# pyr0-piezo_direct_extruder_board2_0_2.net
KiCad netlist of a schematic drawn in EAGLE
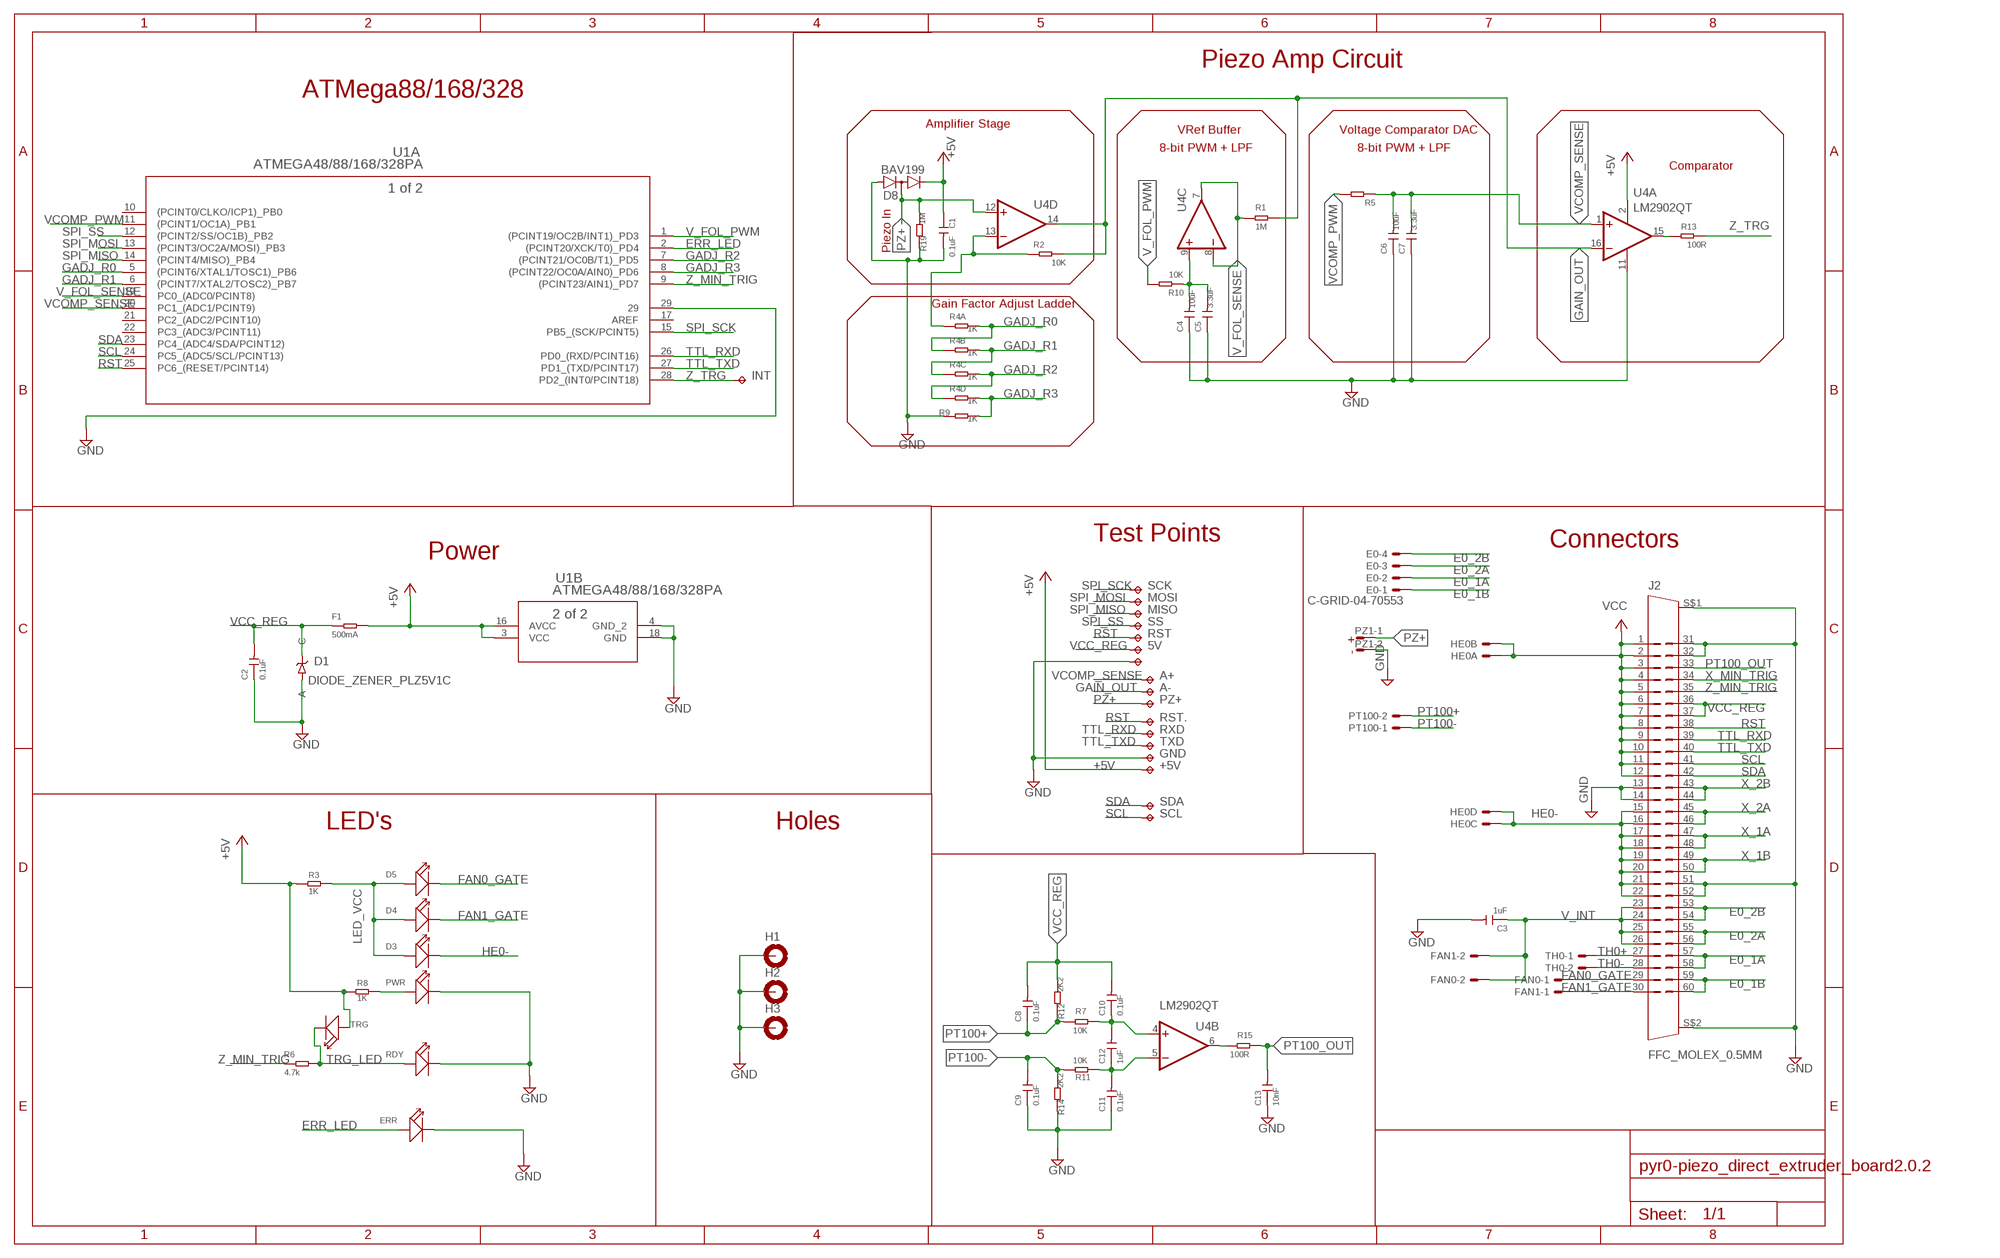
[diagram p0: schematic, sheet 1]

(export (version "E")
  (design (tool "Eeschema 10.0.6"))
  (components
    (comp (ref "+5V")
      (value "TPTP13SQ")
      (footprint "eagle-import:TP13SQ")
      (libsource (lib "eagle-import") (part "testpad_385_TPTP13SQ"))
    )
    (comp (ref "5V")
      (value "TPTP13SQ")
      (footprint "eagle-import:TP13SQ")
      (libsource (lib "eagle-import") (part "TPTP13SQ"))
    )
    (comp (ref "A+")
      (value "TPTP13SQ")
      (footprint "eagle-import:TP13SQ")
      (libsource (lib "eagle-import") (part "TPTP13SQ"))
    )
    (comp (ref "A-")
      (value "TPTP13SQ")
      (footprint "eagle-import:TP13SQ")
      (libsource (lib "eagle-import") (part "TPTP13SQ"))
    )
    (comp (ref "C1")
      (value "0.1uF")
      (footprint "eagle-import:CAPC1005X50")
      (libsource (lib "eagle-import") (part "CERAMIC-1NF-50V-10%-X7R(0402)CAP_0402"))
    )
    (comp (ref "C2")
      (value "0.1uF")
      (footprint "eagle-import:CAPC1005X50")
      (libsource (lib "eagle-import") (part "CERAMIC-1NF-50V-10%-X7R(0402)CAP_0402"))
    )
    (comp (ref "C3")
      (value "1uF")
      (footprint "eagle-import:CAPC1609X80")
      (libsource (lib "eagle-import") (part "SEEED-CAPACITOR_CERAMIC-10UF-25V-10%-X5R(0805)CAP_0603_GEN"))
    )
    (comp (ref "C4")
      (value "10uF")
      (footprint "eagle-import:CAPC1005X50")
      (libsource (lib "eagle-import") (part "CERAMIC-1NF-50V-10%-X7R(0402)CAP_0402"))
    )
    (comp (ref "C5")
      (value "3.3uF")
      (footprint "eagle-import:CAPC1609X80")
      (libsource (lib "eagle-import") (part "SEEED-CAPACITOR_CERAMIC-10UF-25V-10%-X5R(0805)CAP_0603_GEN"))
    )
    (comp (ref "C6")
      (value "10uF")
      (footprint "eagle-import:CAPC1005X50")
      (libsource (lib "eagle-import") (part "CERAMIC-1NF-50V-10%-X7R(0402)CAP_0402"))
    )
    (comp (ref "C7")
      (value "3.3uF")
      (footprint "eagle-import:CAPC1609X80")
      (libsource (lib "eagle-import") (part "SEEED-CAPACITOR_CERAMIC-10UF-25V-10%-X5R(0805)CAP_0603_GEN"))
    )
    (comp (ref "C8")
      (value "0.1uF")
      (footprint "eagle-import:CAPC1005X50")
      (libsource (lib "eagle-import") (part "CERAMIC-1NF-50V-10%-X7R(0402)CAP_0402"))
    )
    (comp (ref "C9")
      (value "0.1uF")
      (footprint "eagle-import:CAPC1005X50")
      (libsource (lib "eagle-import") (part "CERAMIC-1NF-50V-10%-X7R(0402)CAP_0402"))
    )
    (comp (ref "C10")
      (value "0.1uF")
      (footprint "eagle-import:CAPC1005X50")
      (libsource (lib "eagle-import") (part "CERAMIC-1NF-50V-10%-X7R(0402)CAP_0402"))
    )
    (comp (ref "C11")
      (value "0.1uF")
      (footprint "eagle-import:CAPC1005X50")
      (libsource (lib "eagle-import") (part "CERAMIC-1NF-50V-10%-X7R(0402)CAP_0402"))
    )
    (comp (ref "C12")
      (value "1uF")
      (footprint "eagle-import:CAPC1005X50")
      (libsource (lib "eagle-import") (part "CERAMIC-1NF-50V-10%-X7R(0402)CAP_0402"))
    )
    (comp (ref "C13")
      (value "10nF")
      (footprint "eagle-import:CAPC1005X50")
      (libsource (lib "eagle-import") (part "CERAMIC-1NF-50V-10%-X7R(0402)CAP_0402"))
    )
    (comp (ref "D1")
      (value "DIODE_ZENER_PLZ5V1C")
      (footprint "eagle-import:DO-219AC")
      (libsource (lib "eagle-import") (part "DIODE_ZENER_PLZ5V1C"))
    )
    (comp (ref "D3")
      (value "SEEED-LED_SMD-LED-CLEAR-BLUE(0603)LED_0603")
      (footprint "eagle-import:SEEED-LED_LED-0603")
      (libsource (lib "eagle-import") (part "SEEED-LED_SMD-LED-CLEAR-BLUE(0603)LED_0603"))
    )
    (comp (ref "D4")
      (value "SEEED-LED_SMD-LED-CLEAR-BLUE(0603)LED_0603")
      (footprint "eagle-import:SEEED-LED_LED-0603")
      (libsource (lib "eagle-import") (part "SEEED-LED_SMD-LED-CLEAR-BLUE(0603)LED_0603"))
    )
    (comp (ref "D5")
      (value "SEEED-LED_SMD-LED-CLEAR-BLUE(0603)LED_0603")
      (footprint "eagle-import:SEEED-LED_LED-0603")
      (libsource (lib "eagle-import") (part "SEEED-LED_SMD-LED-CLEAR-BLUE(0603)LED_0603"))
    )
    (comp (ref "D8")
      (value "BAV199")
      (footprint "eagle-import:SOT23")
      (libsource (lib "eagle-import") (part "BAV199"))
    )
    (comp (ref "E0")
      (value "C-GRID-04-70553")
      (footprint "eagle-import:70553-04")
      (fields (field (name "MF") "MOLEX"))
      (libsource (lib "eagle-import") (part "C-GRID-04-70553"))
    )
    (comp (ref "ERR")
      (value "SEEED-LED_SMD-LED-CLEAR-BLUE(0603)LED_0603")
      (footprint "eagle-import:SEEED-LED_LED-0603")
      (libsource (lib "eagle-import") (part "SEEED-LED_SMD-LED-CLEAR-BLUE(0603)LED_0603"))
    )
    (comp (ref "F1")
      (value "500mA")
      (footprint "eagle-import:SEEED-RESISTOR_R0603")
      (libsource (lib "eagle-import") (part "SEEED-RESISTOR_SMD-RES-1.5K-1%-1/10W(0603)DETAILED_MODEL"))
    )
    (comp (ref "FAN0")
      (value "CON-MOLEX-2P-1.27MM048")
      (footprint "eagle-import:53048-02")
      (fields (field (name "MF") "MOLEX") (field (name "MPN") "53048-0210"))
      (libsource (lib "eagle-import") (part "CON-MOLEX-2P-1.27MM048"))
    )
    (comp (ref "FAN1")
      (value "CON-MOLEX-2P-1.27MM048")
      (footprint "eagle-import:53048-02")
      (fields (field (name "MF") "MOLEX") (field (name "MPN") "53048-0210"))
      (libsource (lib "eagle-import") (part "CON-MOLEX-2P-1.27MM048"))
    )
    (comp (ref "GND")
      (value "TPTP13SQ")
      (footprint "eagle-import:TP13SQ")
      (libsource (lib "eagle-import") (part "testpad_385_TPTP13SQ"))
    )
    (comp (ref "H1")
      (value "HOLES_MOUNT-PAD-ROUND3.2")
      (footprint "eagle-import:HOLES_3,2-PAD")
      (libsource (lib "eagle-import") (part "HOLES_MOUNT-PAD-ROUND3.2"))
    )
    (comp (ref "H2")
      (value "HOLES_MOUNT-PAD-ROUND3.2")
      (footprint "eagle-import:HOLES_3,2-PAD")
      (libsource (lib "eagle-import") (part "HOLES_MOUNT-PAD-ROUND3.2"))
    )
    (comp (ref "H3")
      (value "HOLES_MOUNT-PAD-ROUND3.2")
      (footprint "eagle-import:HOLES_3,2-PAD")
      (libsource (lib "eagle-import") (part "HOLES_MOUNT-PAD-ROUND3.2"))
    )
    (comp (ref "HE0")
      (value "JST-2.54-2X2JST-DUPONT-2.54-2X2")
      (footprint "eagle-import:HDRRAR4W64P254_2X2_556X736X556B")
      (libsource (lib "eagle-import") (part "JST-2.54-2X2JST-DUPONT-2.54-2X2"))
    )
    (comp (ref "INT")
      (value "TPTP06R")
      (footprint "eagle-import:TP06R")
      (libsource (lib "eagle-import") (part "testpad_385_TPTP06R"))
    )
    (comp (ref "J2")
      (value "FFC_MOLEX_0.5MM")
      (footprint "eagle-import:FFC-60P_0.5_MOLEX_505110-6091")
      (libsource (lib "eagle-import") (part "FFC_MOLEX_0.5MM"))
    )
    (comp (ref "MISO")
      (value "TPTP13SQ")
      (footprint "eagle-import:TP13SQ")
      (libsource (lib "eagle-import") (part "TPTP13SQ"))
    )
    (comp (ref "MOSI")
      (value "TPTP13SQ")
      (footprint "eagle-import:TP13SQ")
      (libsource (lib "eagle-import") (part "TPTP13SQ"))
    )
    (comp (ref "PT100")
      (value "CON-MOLEX-2P-1.27MM048")
      (footprint "eagle-import:53048-02")
      (fields (field (name "MF") "MOLEX") (field (name "MPN") "53048-0210"))
      (libsource (lib "eagle-import") (part "CON-MOLEX-2P-1.27MM048"))
    )
    (comp (ref "PWR")
      (value "SEEED-LED_SMD-LED-CLEAR-BLUE(0603)LED_0603")
      (footprint "eagle-import:SEEED-LED_LED-0603")
      (libsource (lib "eagle-import") (part "SEEED-LED_SMD-LED-CLEAR-BLUE(0603)LED_0603"))
    )
    (comp (ref "PZ+")
      (value "TPTP13SQ")
      (footprint "eagle-import:TP13SQ")
      (libsource (lib "eagle-import") (part "TPTP13SQ"))
    )
    (comp (ref "PZ1")
      (value "CON-MOLEX-2P-1.27MM048")
      (footprint "eagle-import:53048-02")
      (fields (field (name "MF") "MOLEX") (field (name "MPN") "53048-0210"))
      (libsource (lib "eagle-import") (part "CON-MOLEX-2P-1.27MM048"))
    )
    (comp (ref "R1")
      (value "1M")
      (footprint "eagle-import:R0402")
      (fields (field (name "MPN") "RC0402JR-070RL"))
      (libsource (lib "eagle-import") (part "SMD-RES-0R-5%-1/16W(0402)"))
    )
    (comp (ref "R2")
      (value "10K")
      (footprint "eagle-import:R0402")
      (fields (field (name "MPN") "RC0402JR-070RL"))
      (libsource (lib "eagle-import") (part "SMD-RES-0R-5%-1/16W(0402)"))
    )
    (comp (ref "R3")
      (value "1K")
      (footprint "eagle-import:R0402")
      (fields (field (name "MPN") "RC0402JR-070RL"))
      (libsource (lib "eagle-import") (part "SMD-RES-0R-5%-1/16W(0402)"))
    )
    (comp (ref "R4")
      (value "1K")
      (footprint "eagle-import:EXBN8V")
      (libsource (lib "eagle-import") (part "RESISTOR_NETWORK_X40804"))
    )
    (comp (ref "R5")
      (value "10K")
      (footprint "eagle-import:SEEED-RESISTOR_R0603")
      (libsource (lib "eagle-import") (part "SEEED-RESISTOR_SMD-RES-1.5K-1%-1/10W(0603)DETAILED_MODEL"))
    )
    (comp (ref "R6")
      (value "4.7k")
      (footprint "eagle-import:R0402")
      (fields (field (name "MPN") "RC0402JR-070RL"))
      (libsource (lib "eagle-import") (part "SMD-RES-0R-5%-1/16W(0402)"))
    )
    (comp (ref "R7")
      (value "10K")
      (footprint "eagle-import:R0402")
      (fields (field (name "MPN") "RC0402JR-070RL"))
      (libsource (lib "eagle-import") (part "SMD-RES-0R-5%-1/16W(0402)"))
    )
    (comp (ref "R8")
      (value "1K")
      (footprint "eagle-import:R0402")
      (fields (field (name "MPN") "RC0402JR-070RL"))
      (libsource (lib "eagle-import") (part "SMD-RES-0R-5%-1/16W(0402)"))
    )
    (comp (ref "R9")
      (value "1K")
      (footprint "eagle-import:R0402")
      (fields (field (name "MPN") "RC0402JR-070RL"))
      (libsource (lib "eagle-import") (part "SMD-RES-0R-5%-1/16W(0402)"))
    )
    (comp (ref "R10")
      (value "10K")
      (footprint "eagle-import:R0402")
      (fields (field (name "MPN") "RC0402JR-070RL"))
      (libsource (lib "eagle-import") (part "SMD-RES-0R-5%-1/16W(0402)"))
    )
    (comp (ref "R11")
      (value "10K")
      (footprint "eagle-import:R0402")
      (fields (field (name "MPN") "RC0402JR-070RL"))
      (libsource (lib "eagle-import") (part "SMD-RES-0R-5%-1/16W(0402)"))
    )
    (comp (ref "R12")
      (value "2K2")
      (footprint "eagle-import:R0402")
      (fields (field (name "MPN") "RC0402JR-070RL"))
      (libsource (lib "eagle-import") (part "SMD-RES-0R-5%-1/16W(0402)"))
    )
    (comp (ref "R13")
      (value "100R")
      (footprint "eagle-import:R0402")
      (fields (field (name "MPN") "RC0402JR-070RL"))
      (libsource (lib "eagle-import") (part "SMD-RES-0R-5%-1/16W(0402)"))
    )
    (comp (ref "R14")
      (value "2K2")
      (footprint "eagle-import:R0402")
      (fields (field (name "MPN") "RC0402JR-070RL"))
      (libsource (lib "eagle-import") (part "SMD-RES-0R-5%-1/16W(0402)"))
    )
    (comp (ref "R15")
      (value "100R")
      (footprint "eagle-import:R0402")
      (fields (field (name "MPN") "RC0402JR-070RL"))
      (libsource (lib "eagle-import") (part "SMD-RES-0R-5%-1/16W(0402)"))
    )
    (comp (ref "R19")
      (value "1M")
      (footprint "eagle-import:R0402")
      (fields (field (name "MPN") "RC0402JR-070RL"))
      (libsource (lib "eagle-import") (part "SMD-RES-0R-5%-1/16W(0402)"))
    )
    (comp (ref "RDY")
      (value "SEEED-LED_SMD-LED-CLEAR-BLUE(0603)LED_0603")
      (footprint "eagle-import:SEEED-LED_LED-0603")
      (libsource (lib "eagle-import") (part "SEEED-LED_SMD-LED-CLEAR-BLUE(0603)LED_0603"))
    )
    (comp (ref "RST")
      (value "TPTP13SQ")
      (footprint "eagle-import:TP13SQ")
      (libsource (lib "eagle-import") (part "TPTP13SQ"))
    )
    (comp (ref "RST.")
      (value "TPTP13SQ")
      (footprint "eagle-import:TP13SQ")
      (libsource (lib "eagle-import") (part "testpad_385_TPTP13SQ"))
    )
    (comp (ref "RXD")
      (value "TPTP13SQ")
      (footprint "eagle-import:TP13SQ")
      (libsource (lib "eagle-import") (part "testpad_385_TPTP13SQ"))
    )
    (comp (ref "SCK")
      (value "TPTP13SQ")
      (footprint "eagle-import:TP13SQ")
      (libsource (lib "eagle-import") (part "TPTP13SQ"))
    )
    (comp (ref "SCL")
      (value "TPTP13SQ")
      (footprint "eagle-import:TP13SQ")
      (libsource (lib "eagle-import") (part "testpad_385_TPTP13SQ"))
    )
    (comp (ref "SDA")
      (value "TPTP13SQ")
      (footprint "eagle-import:TP13SQ")
      (libsource (lib "eagle-import") (part "testpad_385_TPTP13SQ"))
    )
    (comp (ref "SS")
      (value "TPTP06R")
      (footprint "eagle-import:TP06R")
      (libsource (lib "eagle-import") (part "testpad_385_TPTP06R"))
    )
    (comp (ref "TH0")
      (value "CON-MOLEX-2P-1.27MM048")
      (footprint "eagle-import:53048-02")
      (fields (field (name "MF") "MOLEX") (field (name "MPN") "53048-0210"))
      (libsource (lib "eagle-import") (part "CON-MOLEX-2P-1.27MM048"))
    )
    (comp (ref "TRG")
      (value "SEEED-LED_SMD-LED-CLEAR-BLUE(0603)LED_0603")
      (footprint "eagle-import:SEEED-LED_LED-0603")
      (libsource (lib "eagle-import") (part "SEEED-LED_SMD-LED-CLEAR-BLUE(0603)LED_0603"))
    )
    (comp (ref "TXD")
      (value "TPTP13SQ")
      (footprint "eagle-import:TP13SQ")
      (libsource (lib "eagle-import") (part "testpad_385_TPTP13SQ"))
    )
    (comp (ref "U1")
      (value "ATMEGA48/88/168/328PA")
      (footprint "eagle-import:28M1")
      (fields (field (name "MANUFACTURER_PART_NUMBER") "ATMEGA48PAMMHR"))
      (libsource (lib "eagle-import") (part "ATMEGA48/88/168/328PA"))
    )
    (comp (ref "U4")
      (value "LM2902QT")
      (footprint "eagle-import:QFN16")
      (libsource (lib "eagle-import") (part "LM2902QT"))
    )
    (comp (ref "⏚")
      (value "TPTP13SQ")
      (footprint "eagle-import:TP13SQ")
      (libsource (lib "eagle-import") (part "testpad_385_TPTP13SQ"))
    )
  )
  (nets
    (net (code "1") (name "+5V") (class "Default")
      (node (ref "+5V") (pin "TP") (pinfunction "TP_TP") (pintype "input"))
      (node (ref "C1") (pin "1") (pinfunction "1_1") (pintype "passive"))
      (node (ref "D8") (pin "2") (pinfunction "C_2") (pintype "passive"))
      (node (ref "F1") (pin "2") (pinfunction "2_2") (pintype "passive"))
      (node (ref "R3") (pin "1") (pinfunction "1_1") (pintype "passive"))
      (node (ref "R8") (pin "1") (pinfunction "1_1") (pintype "passive"))
      (node (ref "TRG") (pin "+") (pinfunction "+_+") (pintype "passive"))
      (node (ref "U1") (pin "16") (pinfunction "AVCC_16") (pintype "power_in"))
      (node (ref "U1") (pin "3") (pinfunction "VCC_3") (pintype "power_in"))
      (node (ref "U4") (pin "2") (pinfunction "V+_2") (pintype "power_in"))
    )
    (net (code "2") (name "/E0_1A") (class "Default")
      (node (ref "E0") (pin "2") (pinfunction "S_2") (pintype "passive"))
      (node (ref "J2") (pin "57") (pinfunction "63_57") (pintype "passive"))
      (node (ref "J2") (pin "58") (pinfunction "64_58") (pintype "passive"))
    )
    (net (code "3") (name "/E0_1B") (class "Default")
      (node (ref "E0") (pin "1") (pinfunction "S_1") (pintype "passive"))
      (node (ref "J2") (pin "59") (pinfunction "65_59") (pintype "passive"))
      (node (ref "J2") (pin "60") (pinfunction "66_60") (pintype "passive"))
    )
    (net (code "4") (name "/E0_2A") (class "Default")
      (node (ref "E0") (pin "3") (pinfunction "S_3") (pintype "passive"))
      (node (ref "J2") (pin "55") (pinfunction "61_55") (pintype "passive"))
      (node (ref "J2") (pin "56") (pinfunction "62_56") (pintype "passive"))
    )
    (net (code "5") (name "/E0_2B") (class "Default")
      (node (ref "E0") (pin "4") (pinfunction "S_4") (pintype "passive"))
      (node (ref "J2") (pin "53") (pinfunction "59_53") (pintype "passive"))
      (node (ref "J2") (pin "54") (pinfunction "60_54") (pintype "passive"))
    )
    (net (code "6") (name "/ERR_LED") (class "Default")
      (node (ref "ERR") (pin "+") (pinfunction "+_+") (pintype "passive"))
      (node (ref "U1") (pin "2") (pinfunction "(PCINT20/XCK/T0)_PD4_2") (pintype "bidirectional"))
    )
    (net (code "7") (name "/FAN0_GATE") (class "Default")
      (node (ref "D5") (pin "-") (pinfunction "-_-") (pintype "passive"))
      (node (ref "FAN0") (pin "1") (pinfunction "S_1") (pintype "passive"))
      (node (ref "J2") (pin "29") (pinfunction "31_29") (pintype "passive"))
    )
    (net (code "8") (name "/FAN1_GATE") (class "Default")
      (node (ref "D4") (pin "-") (pinfunction "-_-") (pintype "passive"))
      (node (ref "FAN1") (pin "1") (pinfunction "S_1") (pintype "passive"))
      (node (ref "J2") (pin "30") (pinfunction "32_30") (pintype "passive"))
    )
    (net (code "9") (name "/GADJ_R0") (class "Default")
      (node (ref "R4") (pin "2") (pinfunction "1_2") (pintype "passive"))
      (node (ref "R4") (pin "8") (pinfunction "2_8") (pintype "passive"))
      (node (ref "U1") (pin "5") (pinfunction "(PCINT6/XTAL1/TOSC1)_PB6_5") (pintype "bidirectional"))
    )
    (net (code "10") (name "/GADJ_R1") (class "Default")
      (node (ref "R4") (pin "3") (pinfunction "1_3") (pintype "passive"))
      (node (ref "R4") (pin "7") (pinfunction "2_7") (pintype "passive"))
      (node (ref "U1") (pin "6") (pinfunction "(PCINT7/XTAL2/TOSC2)_PB7_6") (pintype "bidirectional"))
    )
    (net (code "11") (name "/GADJ_R2") (class "Default")
      (node (ref "R4") (pin "4") (pinfunction "1_4") (pintype "passive"))
      (node (ref "R4") (pin "6") (pinfunction "2_6") (pintype "passive"))
      (node (ref "U1") (pin "7") (pinfunction "(PCINT21/OC0B/T1)_PD5_7") (pintype "bidirectional"))
    )
    (net (code "12") (name "/GADJ_R3") (class "Default")
      (node (ref "R4") (pin "5") (pinfunction "2_5") (pintype "passive"))
      (node (ref "R9") (pin "2") (pinfunction "2_2") (pintype "passive"))
      (node (ref "U1") (pin "8") (pinfunction "(PCINT22/OC0A/AIN0)_PD6_8") (pintype "bidirectional"))
    )
    (net (code "13") (name "/HE0-") (class "Default")
      (node (ref "D3") (pin "-") (pinfunction "-_-") (pintype "passive"))
      (node (ref "HE0") (pin "3") (pinfunction "S_3") (pintype "passive"))
      (node (ref "HE0") (pin "4") (pinfunction "S_4") (pintype "passive"))
      (node (ref "J2") (pin "15") (pinfunction "17_15") (pintype "passive"))
      (node (ref "J2") (pin "16") (pinfunction "18_16") (pintype "passive"))
      (node (ref "J2") (pin "17") (pinfunction "19_17") (pintype "passive"))
      (node (ref "J2") (pin "18") (pinfunction "20_18") (pintype "passive"))
      (node (ref "J2") (pin "19") (pinfunction "21_19") (pintype "passive"))
      (node (ref "J2") (pin "20") (pinfunction "22_20") (pintype "passive"))
      (node (ref "J2") (pin "21") (pinfunction "23_21") (pintype "passive"))
      (node (ref "J2") (pin "22") (pinfunction "24_22") (pintype "passive"))
    )
    (net (code "14") (name "/LED_VCC") (class "Default")
      (node (ref "D3") (pin "+") (pinfunction "+_+") (pintype "passive"))
      (node (ref "D4") (pin "+") (pinfunction "+_+") (pintype "passive"))
      (node (ref "D5") (pin "+") (pinfunction "+_+") (pintype "passive"))
      (node (ref "R3") (pin "2") (pinfunction "2_2") (pintype "passive"))
    )
    (net (code "15") (name "/RST") (class "Default")
      (node (ref "J2") (pin "38") (pinfunction "44_38") (pintype "passive"))
      (node (ref "RST") (pin "TP") (pinfunction "TP_TP") (pintype "input"))
      (node (ref "RST.") (pin "TP") (pinfunction "TP_TP") (pintype "input"))
      (node (ref "U1") (pin "25") (pinfunction "PC6_(RESET/PCINT14)_25") (pintype "bidirectional"))
    )
    (net (code "16") (name "/SCL") (class "Default")
      (node (ref "J2") (pin "41") (pinfunction "47_41") (pintype "passive"))
      (node (ref "SCL") (pin "TP") (pinfunction "TP_TP") (pintype "input"))
      (node (ref "U1") (pin "24") (pinfunction "PC5_(ADC5/SCL/PCINT13)_24") (pintype "bidirectional"))
    )
    (net (code "17") (name "/SDA") (class "Default")
      (node (ref "J2") (pin "42") (pinfunction "48_42") (pintype "passive"))
      (node (ref "SDA") (pin "TP") (pinfunction "TP_TP") (pintype "input"))
      (node (ref "U1") (pin "23") (pinfunction "PC4_(ADC4/SDA/PCINT12)_23") (pintype "bidirectional"))
    )
    (net (code "18") (name "/SPI_MISO") (class "Default")
      (node (ref "MISO") (pin "TP") (pinfunction "TP_TP") (pintype "input"))
      (node (ref "U1") (pin "14") (pinfunction "(PCINT4/MISO)_PB4_14") (pintype "bidirectional"))
    )
    (net (code "19") (name "/SPI_MOSI") (class "Default")
      (node (ref "MOSI") (pin "TP") (pinfunction "TP_TP") (pintype "input"))
      (node (ref "U1") (pin "13") (pinfunction "(PCINT3/OC2A/MOSI)_PB3_13") (pintype "bidirectional"))
    )
    (net (code "20") (name "/SPI_SCK") (class "Default")
      (node (ref "SCK") (pin "TP") (pinfunction "TP_TP") (pintype "input"))
      (node (ref "U1") (pin "15") (pinfunction "PB5_(SCK/PCINT5)_15") (pintype "bidirectional"))
    )
    (net (code "21") (name "/SPI_SS") (class "Default")
      (node (ref "SS") (pin "TP") (pinfunction "TP_TP") (pintype "input"))
      (node (ref "U1") (pin "12") (pinfunction "(PCINT2/SS/OC1B)_PB2_12") (pintype "bidirectional"))
    )
    (net (code "22") (name "/TH0+") (class "Default")
      (node (ref "J2") (pin "27") (pinfunction "29_27") (pintype "passive"))
      (node (ref "TH0") (pin "1") (pinfunction "S_1") (pintype "passive"))
    )
    (net (code "23") (name "/TH0-") (class "Default")
      (node (ref "J2") (pin "28") (pinfunction "30_28") (pintype "passive"))
      (node (ref "TH0") (pin "2") (pinfunction "S_2") (pintype "passive"))
    )
    (net (code "24") (name "/TRG_LED") (class "Default")
      (node (ref "R6") (pin "2") (pinfunction "2_2") (pintype "passive"))
      (node (ref "RDY") (pin "+") (pinfunction "+_+") (pintype "passive"))
      (node (ref "TRG") (pin "-") (pinfunction "-_-") (pintype "passive"))
    )
    (net (code "25") (name "/TTL_RXD") (class "Default")
      (node (ref "J2") (pin "39") (pinfunction "45_39") (pintype "passive"))
      (node (ref "RXD") (pin "TP") (pinfunction "TP_TP") (pintype "input"))
      (node (ref "U1") (pin "26") (pinfunction "PD0_(RXD/PCINT16)_26") (pintype "bidirectional"))
    )
    (net (code "26") (name "/TTL_TXD") (class "Default")
      (node (ref "J2") (pin "40") (pinfunction "46_40") (pintype "passive"))
      (node (ref "TXD") (pin "TP") (pinfunction "TP_TP") (pintype "input"))
      (node (ref "U1") (pin "27") (pinfunction "PD1_(TXD/PCINT17)_27") (pintype "bidirectional"))
    )
    (net (code "27") (name "/V_INT") (class "Default")
      (node (ref "C3") (pin "1") (pinfunction "1_1") (pintype "passive"))
      (node (ref "FAN0") (pin "2") (pinfunction "S_2") (pintype "passive"))
      (node (ref "FAN1") (pin "2") (pinfunction "S_2") (pintype "passive"))
      (node (ref "J2") (pin "23") (pinfunction "25_23") (pintype "passive"))
      (node (ref "J2") (pin "24") (pinfunction "26_24") (pintype "passive"))
      (node (ref "J2") (pin "25") (pinfunction "27_25") (pintype "passive"))
      (node (ref "J2") (pin "26") (pinfunction "28_26") (pintype "passive"))
    )
    (net (code "28") (name "/X_1A") (class "Default")
      (node (ref "J2") (pin "47") (pinfunction "53_47") (pintype "passive"))
      (node (ref "J2") (pin "48") (pinfunction "54_48") (pintype "passive"))
    )
    (net (code "29") (name "/X_1B") (class "Default")
      (node (ref "J2") (pin "49") (pinfunction "55_49") (pintype "passive"))
      (node (ref "J2") (pin "50") (pinfunction "56_50") (pintype "passive"))
    )
    (net (code "30") (name "/X_2A") (class "Default")
      (node (ref "J2") (pin "45") (pinfunction "51_45") (pintype "passive"))
      (node (ref "J2") (pin "46") (pinfunction "52_46") (pintype "passive"))
    )
    (net (code "31") (name "/X_2B") (class "Default")
      (node (ref "J2") (pin "43") (pinfunction "49_43") (pintype "passive"))
      (node (ref "J2") (pin "44") (pinfunction "50_44") (pintype "passive"))
    )
    (net (code "32") (name "/X_MIN_TRIG") (class "Default")
      (node (ref "J2") (pin "34") (pinfunction "40_34") (pintype "passive"))
    )
    (net (code "33") (name "/Z_MIN_TRIG") (class "Default")
      (node (ref "J2") (pin "35") (pinfunction "41_35") (pintype "passive"))
      (node (ref "R6") (pin "1") (pinfunction "1_1") (pintype "passive"))
      (node (ref "U1") (pin "9") (pinfunction "(PCINT23/AIN1)_PD7_9") (pintype "bidirectional"))
    )
    (net (code "34") (name "/Z_TRG") (class "Default")
      (node (ref "INT") (pin "TP") (pinfunction "TP_TP") (pintype "input"))
      (node (ref "R13") (pin "2") (pinfunction "2_2") (pintype "passive"))
      (node (ref "U1") (pin "28") (pinfunction "PD2_(INT0/PCINT18)_28") (pintype "bidirectional"))
    )
    (net (code "35") (name "GAIN_OUT") (class "Default")
      (node (ref "A-") (pin "TP") (pinfunction "TP_TP") (pintype "input"))
      (node (ref "R1") (pin "2") (pinfunction "2_2") (pintype "passive"))
      (node (ref "R2") (pin "2") (pinfunction "2_2") (pintype "passive"))
      (node (ref "U4") (pin "14") (pinfunction "OUT_14") (pintype "output"))
      (node (ref "U4") (pin "16") (pinfunction "-IN_16") (pintype "input"))
    )
    (net (code "36") (name "GND") (class "Default")
      (node (ref "C1") (pin "2") (pinfunction "2_2") (pintype "passive"))
      (node (ref "C11") (pin "1") (pinfunction "1_1") (pintype "passive"))
      (node (ref "C13") (pin "1") (pinfunction "1_1") (pintype "passive"))
      (node (ref "C2") (pin "1") (pinfunction "1_1") (pintype "passive"))
      (node (ref "C3") (pin "2") (pinfunction "2_2") (pintype "passive"))
      (node (ref "C4") (pin "1") (pinfunction "1_1") (pintype "passive"))
      (node (ref "C5") (pin "1") (pinfunction "1_1") (pintype "passive"))
      (node (ref "C6") (pin "1") (pinfunction "1_1") (pintype "passive"))
      (node (ref "C7") (pin "1") (pinfunction "1_1") (pintype "passive"))
      (node (ref "C9") (pin "1") (pinfunction "1_1") (pintype "passive"))
      (node (ref "D1") (pin "P$1") (pinfunction "A_P$1") (pintype "passive"))
      (node (ref "D8") (pin "1") (pinfunction "A_1") (pintype "passive"))
      (node (ref "ERR") (pin "-") (pinfunction "-_-") (pintype "passive"))
      (node (ref "GND") (pin "TP") (pinfunction "TP_TP") (pintype "input"))
      (node (ref "H1") (pin "B3,2") (pinfunction "MOUNT_B3,2") (pintype "passive"))
      (node (ref "H2") (pin "B3,2") (pinfunction "MOUNT_B3,2") (pintype "passive"))
      (node (ref "H3") (pin "B3,2") (pinfunction "MOUNT_B3,2") (pintype "passive"))
      (node (ref "J2") (pin "13") (pinfunction "15_13") (pintype "passive"))
      (node (ref "J2") (pin "14") (pinfunction "16_14") (pintype "passive"))
      (node (ref "J2") (pin "31") (pinfunction "37_31") (pintype "passive"))
      (node (ref "J2") (pin "32") (pinfunction "38_32") (pintype "passive"))
      (node (ref "J2") (pin "51") (pinfunction "57_51") (pintype "passive"))
      (node (ref "J2") (pin "52") (pinfunction "58_52") (pintype "passive"))
      (node (ref "J2") (pin "S$1") (pinfunction "S_S$1") (pintype "passive"))
      (node (ref "J2") (pin "S$2") (pinfunction "S_S$2") (pintype "passive"))
      (node (ref "PWR") (pin "-") (pinfunction "-_-") (pintype "passive"))
      (node (ref "PZ1") (pin "2") (pinfunction "S_2") (pintype "passive"))
      (node (ref "R14") (pin "1") (pinfunction "1_1") (pintype "passive"))
      (node (ref "R19") (pin "1") (pinfunction "1_1") (pintype "passive"))
      (node (ref "R9") (pin "1") (pinfunction "1_1") (pintype "passive"))
      (node (ref "RDY") (pin "-") (pinfunction "-_-") (pintype "passive"))
      (node (ref "U1") (pin "18") (pinfunction "GND_18") (pintype "power_in"))
      (node (ref "U1") (pin "29") (pinfunction "29_29") (pintype "passive"))
      (node (ref "U1") (pin "4") (pinfunction "GND_2_4") (pintype "power_in"))
      (node (ref "U4") (pin "11") (pinfunction "V-_11") (pintype "power_in"))
      (node (ref "⏚") (pin "TP") (pinfunction "TP_TP") (pintype "input"))
    )
    (net (code "37") (name "Net-(PWR-Pad+)") (class "Default")
      (node (ref "PWR") (pin "+") (pinfunction "+_+") (pintype "passive"))
      (node (ref "R8") (pin "2") (pinfunction "2_2") (pintype "passive"))
    )
    (net (code "38") (name "Net-(U4A-OUT)") (class "Default")
      (node (ref "R13") (pin "1") (pinfunction "1_1") (pintype "passive"))
      (node (ref "U4") (pin "15") (pinfunction "OUT_15") (pintype "output"))
    )
    (net (code "39") (name "Net-(U4B-+IN)") (class "Default")
      (node (ref "C10") (pin "1") (pinfunction "1_1") (pintype "passive"))
      (node (ref "C12") (pin "2") (pinfunction "2_2") (pintype "passive"))
      (node (ref "R7") (pin "1") (pinfunction "1_1") (pintype "passive"))
      (node (ref "U4") (pin "4") (pinfunction "+IN_4") (pintype "input"))
    )
    (net (code "40") (name "Net-(U4B--IN)") (class "Default")
      (node (ref "C11") (pin "2") (pinfunction "2_2") (pintype "passive"))
      (node (ref "C12") (pin "1") (pinfunction "1_1") (pintype "passive"))
      (node (ref "R11") (pin "1") (pinfunction "1_1") (pintype "passive"))
      (node (ref "U4") (pin "5") (pinfunction "-IN_5") (pintype "input"))
    )
    (net (code "41") (name "Net-(U4B-OUT)") (class "Default")
      (node (ref "R15") (pin "2") (pinfunction "2_2") (pintype "passive"))
      (node (ref "U4") (pin "6") (pinfunction "OUT_6") (pintype "output"))
    )
    (net (code "42") (name "Net-(U4C-+IN)") (class "Default")
      (node (ref "C4") (pin "2") (pinfunction "2_2") (pintype "passive"))
      (node (ref "C5") (pin "2") (pinfunction "2_2") (pintype "passive"))
      (node (ref "R10") (pin "1") (pinfunction "1_1") (pintype "passive"))
      (node (ref "U4") (pin "9") (pinfunction "+IN_9") (pintype "input"))
    )
    (net (code "43") (name "Net-(U4D--IN)") (class "Default")
      (node (ref "R2") (pin "1") (pinfunction "1_1") (pintype "passive"))
      (node (ref "R4") (pin "1") (pinfunction "1_1") (pintype "passive"))
      (node (ref "U4") (pin "13") (pinfunction "-IN_13") (pintype "input"))
    )
    (net (code "44") (name "PT100+") (class "Default")
      (node (ref "C8") (pin "1") (pinfunction "1_1") (pintype "passive"))
      (node (ref "PT100") (pin "2") (pinfunction "S_2") (pintype "passive"))
      (node (ref "R12") (pin "1") (pinfunction "1_1") (pintype "passive"))
      (node (ref "R7") (pin "2") (pinfunction "2_2") (pintype "passive"))
    )
    (net (code "45") (name "PT100-") (class "Default")
      (node (ref "C9") (pin "2") (pinfunction "2_2") (pintype "passive"))
      (node (ref "PT100") (pin "1") (pinfunction "S_1") (pintype "passive"))
      (node (ref "R11") (pin "2") (pinfunction "2_2") (pintype "passive"))
      (node (ref "R14") (pin "2") (pinfunction "2_2") (pintype "passive"))
    )
    (net (code "46") (name "PT100_OUT") (class "Default")
      (node (ref "C13") (pin "2") (pinfunction "2_2") (pintype "passive"))
      (node (ref "J2") (pin "33") (pinfunction "39_33") (pintype "passive"))
      (node (ref "R15") (pin "1") (pinfunction "1_1") (pintype "passive"))
    )
    (net (code "47") (name "PZ+") (class "Default")
      (node (ref "D8") (pin "3") (pinfunction "AC_3") (pintype "passive"))
      (node (ref "PZ+") (pin "TP") (pinfunction "TP_TP") (pintype "input"))
      (node (ref "PZ1") (pin "1") (pinfunction "S_1") (pintype "passive"))
      (node (ref "R19") (pin "2") (pinfunction "2_2") (pintype "passive"))
      (node (ref "U4") (pin "12") (pinfunction "+IN_12") (pintype "input"))
    )
    (net (code "48") (name "VCC") (class "Default")
      (node (ref "HE0") (pin "1") (pinfunction "S_1") (pintype "passive"))
      (node (ref "HE0") (pin "2") (pinfunction "S_2") (pintype "passive"))
      (node (ref "J2") (pin "1") (pinfunction "3_1") (pintype "passive"))
      (node (ref "J2") (pin "10") (pinfunction "12_10") (pintype "passive"))
      (node (ref "J2") (pin "11") (pinfunction "13_11") (pintype "passive"))
      (node (ref "J2") (pin "12") (pinfunction "14_12") (pintype "passive"))
      (node (ref "J2") (pin "2") (pinfunction "4_2") (pintype "passive"))
      (node (ref "J2") (pin "3") (pinfunction "5_3") (pintype "passive"))
      (node (ref "J2") (pin "4") (pinfunction "6_4") (pintype "passive"))
      (node (ref "J2") (pin "5") (pinfunction "7_5") (pintype "passive"))
      (node (ref "J2") (pin "6") (pinfunction "8_6") (pintype "passive"))
      (node (ref "J2") (pin "7") (pinfunction "9_7") (pintype "passive"))
      (node (ref "J2") (pin "8") (pinfunction "10_8") (pintype "passive"))
      (node (ref "J2") (pin "9") (pinfunction "11_9") (pintype "passive"))
    )
    (net (code "49") (name "VCC_REG") (class "Default")
      (node (ref "5V") (pin "TP") (pinfunction "TP_TP") (pintype "input"))
      (node (ref "C10") (pin "2") (pinfunction "2_2") (pintype "passive"))
      (node (ref "C2") (pin "2") (pinfunction "2_2") (pintype "passive"))
      (node (ref "C8") (pin "2") (pinfunction "2_2") (pintype "passive"))
      (node (ref "D1") (pin "P$2") (pinfunction "C_P$2") (pintype "passive"))
      (node (ref "F1") (pin "1") (pinfunction "1_1") (pintype "passive"))
      (node (ref "J2") (pin "36") (pinfunction "42_36") (pintype "passive"))
      (node (ref "J2") (pin "37") (pinfunction "43_37") (pintype "passive"))
      (node (ref "R12") (pin "2") (pinfunction "2_2") (pintype "passive"))
    )
    (net (code "50") (name "VCOMP_PWM") (class "Default")
      (node (ref "R5") (pin "2") (pinfunction "2_2") (pintype "passive"))
      (node (ref "U1") (pin "11") (pinfunction "(PCINT1/OC1A)_PB1_11") (pintype "bidirectional"))
    )
    (net (code "51") (name "VCOMP_SENSE") (class "Default")
      (node (ref "A+") (pin "TP") (pinfunction "TP_TP") (pintype "input"))
      (node (ref "C6") (pin "2") (pinfunction "2_2") (pintype "passive"))
      (node (ref "C7") (pin "2") (pinfunction "2_2") (pintype "passive"))
      (node (ref "R5") (pin "1") (pinfunction "1_1") (pintype "passive"))
      (node (ref "U1") (pin "20") (pinfunction "PC1_(ADC1/PCINT9)_20") (pintype "bidirectional"))
      (node (ref "U4") (pin "1") (pinfunction "+IN_1") (pintype "input"))
    )
    (net (code "52") (name "V_FOL_PWM") (class "Default")
      (node (ref "R10") (pin "2") (pinfunction "2_2") (pintype "passive"))
      (node (ref "U1") (pin "1") (pinfunction "(PCINT19/OC2B/INT1)_PD3_1") (pintype "bidirectional"))
    )
    (net (code "53") (name "V_FOL_SENSE") (class "Default")
      (node (ref "R1") (pin "1") (pinfunction "1_1") (pintype "passive"))
      (node (ref "U1") (pin "19") (pinfunction "PC0_(ADC0/PCINT8)_19") (pintype "bidirectional"))
      (node (ref "U4") (pin "7") (pinfunction "OUT_7") (pintype "output"))
      (node (ref "U4") (pin "8") (pinfunction "-IN_8") (pintype "input"))
    )
    (net (code "54") (name "unconnected-(U1A-(PCINT0{slash}CLKO{slash}ICP1)_PB0-Pad10)") (class "Default")
      (node (ref "U1") (pin "10") (pinfunction "(PCINT0/CLKO/ICP1)_PB0_10") (pintype "bidirectional"))
    )
    (net (code "55") (name "unconnected-(U1A-AREF-Pad17)") (class "Default")
      (node (ref "U1") (pin "17") (pinfunction "AREF_17") (pintype "passive"))
    )
    (net (code "56") (name "unconnected-(U1A-PC2_(ADC2{slash}PCINT10)-Pad21)") (class "Default")
      (node (ref "U1") (pin "21") (pinfunction "PC2_(ADC2/PCINT10)_21") (pintype "bidirectional"))
    )
    (net (code "57") (name "unconnected-(U1A-PC3_(ADC3{slash}PCINT11)-Pad22)") (class "Default")
      (node (ref "U1") (pin "22") (pinfunction "PC3_(ADC3/PCINT11)_22") (pintype "bidirectional"))
    )
  )
)
